# Sheet1.net
KiCad netlist of a schematic drawn in Altium Designer
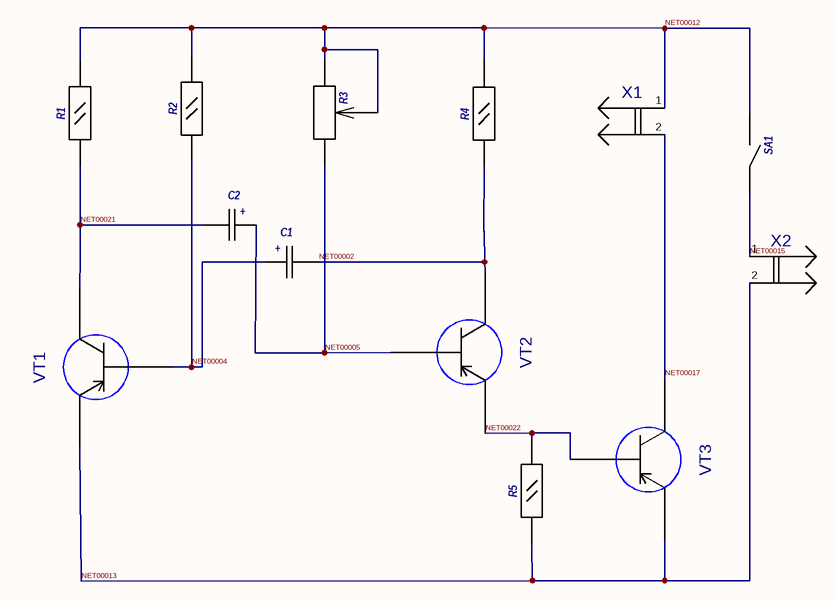
[diagram p0: Sheet1.SCHDOC]

(export (version "E")
  (design (tool "Eeschema 10.0.6"))
  (components
    (comp (ref "C1")
      (value "K50-29 (1;2,2;4,7;10;22 MK)")
      (footprint "К50-29 (17Х6)")
      (libsource (lib "*") (part "K50-29 (1;2,2;4,7;10;22 MK)"))
    )
    (comp (ref "C2")
      (value "K50-29 (1;2,2;4,7;10;22 MK)")
      (footprint "К50-29 (17Х6)")
      (libsource (lib "*") (part "K50-29 (1;2,2;4,7;10;22 MK)"))
    )
    (comp (ref "R1") (value "МЛТ(0.125)") (footprint "МЛТ(0.125)") (libsource (lib "*") (part "МЛТ(0.125)")))
    (comp (ref "R2") (value "МЛТ(0.125)") (footprint "МЛТ(0.125)") (libsource (lib "*") (part "МЛТ(0.125)")))
    (comp (ref "R3") (value "СП3-38В") (footprint "СП3-38В") (libsource (lib "*") (part "СП3-38В")))
    (comp (ref "R4") (value "МЛТ(0.125)") (footprint "МЛТ(0.125)") (libsource (lib "*") (part "МЛТ(0.125)")))
    (comp (ref "R5") (value "МЛТ(0.125)") (footprint "МЛТ(0.125)") (libsource (lib "") (part "МЛТ(0.125)_1")))
    (comp (ref "SA1") (value "T1") (footprint "Т1") (libsource (lib "*") (part "T1")))
    (comp (ref "VT1") (value "КТ837") (footprint "КТ837") (libsource (lib "*") (part "КТ837")))
    (comp (ref "VT2") (value "КТ837") (footprint "КТ837") (libsource (lib "") (part "КТ837_1")))
    (comp (ref "VT3") (value "КТ837") (footprint "КТ837") (libsource (lib "") (part "КТ837_1")))
    (comp (ref "X1") (value "2XR") (footprint "2XR") (libsource (lib "*") (part "2XR")))
    (comp (ref "X2") (value "2XR") (footprint "2XR") (libsource (lib "") (part "2XR_1")))
  )
  (nets
    (net (code "1") (name "/NET00002") (class "Default")
      (node (ref "C1") (pin "1") (pinfunction "1_1") (pintype "passive"))
      (node (ref "R4") (pin "1") (pinfunction "1_1") (pintype "passive"))
      (node (ref "VT2") (pin "2") (pinfunction "A2_2") (pintype "passive"))
    )
    (net (code "2") (name "/NET00004") (class "Default")
      (node (ref "C1") (pin "2") (pinfunction "2_2") (pintype "passive"))
      (node (ref "R2") (pin "1") (pinfunction "1_1") (pintype "passive"))
      (node (ref "VT1") (pin "1") (pinfunction "A1_1") (pintype "passive"))
    )
    (net (code "3") (name "/NET00005") (class "Default")
      (node (ref "C2") (pin "2") (pinfunction "2_2") (pintype "passive"))
      (node (ref "R3") (pin "1") (pinfunction "1_1") (pintype "passive"))
      (node (ref "VT2") (pin "1") (pinfunction "A1_1") (pintype "passive"))
    )
    (net (code "4") (name "/NET00012") (class "Default")
      (node (ref "R1") (pin "2") (pinfunction "2_2") (pintype "passive"))
      (node (ref "R2") (pin "2") (pinfunction "2_2") (pintype "passive"))
      (node (ref "R3") (pin "2") (pinfunction "2_2") (pintype "passive"))
      (node (ref "R3") (pin "3") (pinfunction "3_3") (pintype "passive"))
      (node (ref "R4") (pin "2") (pinfunction "2_2") (pintype "passive"))
      (node (ref "SA1") (pin "2") (pinfunction "2_2") (pintype "passive"))
      (node (ref "X1") (pin "1") (pinfunction "I/O1_1") (pintype "passive"))
    )
    (net (code "5") (name "/NET00013") (class "Default")
      (node (ref "R5") (pin "1") (pinfunction "1_1") (pintype "passive"))
      (node (ref "VT1") (pin "3") (pinfunction "A3_3") (pintype "passive"))
      (node (ref "VT3") (pin "3") (pinfunction "A3_3") (pintype "passive"))
      (node (ref "X2") (pin "2") (pinfunction "I/O2_2") (pintype "passive"))
    )
    (net (code "6") (name "/NET00015") (class "Default")
      (node (ref "SA1") (pin "1") (pinfunction "1_1") (pintype "passive"))
      (node (ref "X2") (pin "1") (pinfunction "I/O1_1") (pintype "passive"))
    )
    (net (code "7") (name "/NET00017") (class "Default")
      (node (ref "VT3") (pin "2") (pinfunction "A2_2") (pintype "passive"))
      (node (ref "X1") (pin "2") (pinfunction "I/O2_2") (pintype "passive"))
    )
    (net (code "8") (name "/NET00021") (class "Default")
      (node (ref "C2") (pin "1") (pinfunction "1_1") (pintype "passive"))
      (node (ref "R1") (pin "1") (pinfunction "1_1") (pintype "passive"))
      (node (ref "VT1") (pin "2") (pinfunction "A2_2") (pintype "passive"))
    )
    (net (code "9") (name "/NET00022") (class "Default")
      (node (ref "R5") (pin "2") (pinfunction "2_2") (pintype "passive"))
      (node (ref "VT2") (pin "3") (pinfunction "A3_3") (pintype "passive"))
      (node (ref "VT3") (pin "1") (pinfunction "A1_1") (pintype "passive"))
    )
  )
)
